# RJ45_1.net
KiCad netlist of a schematic drawn in Altium Designer
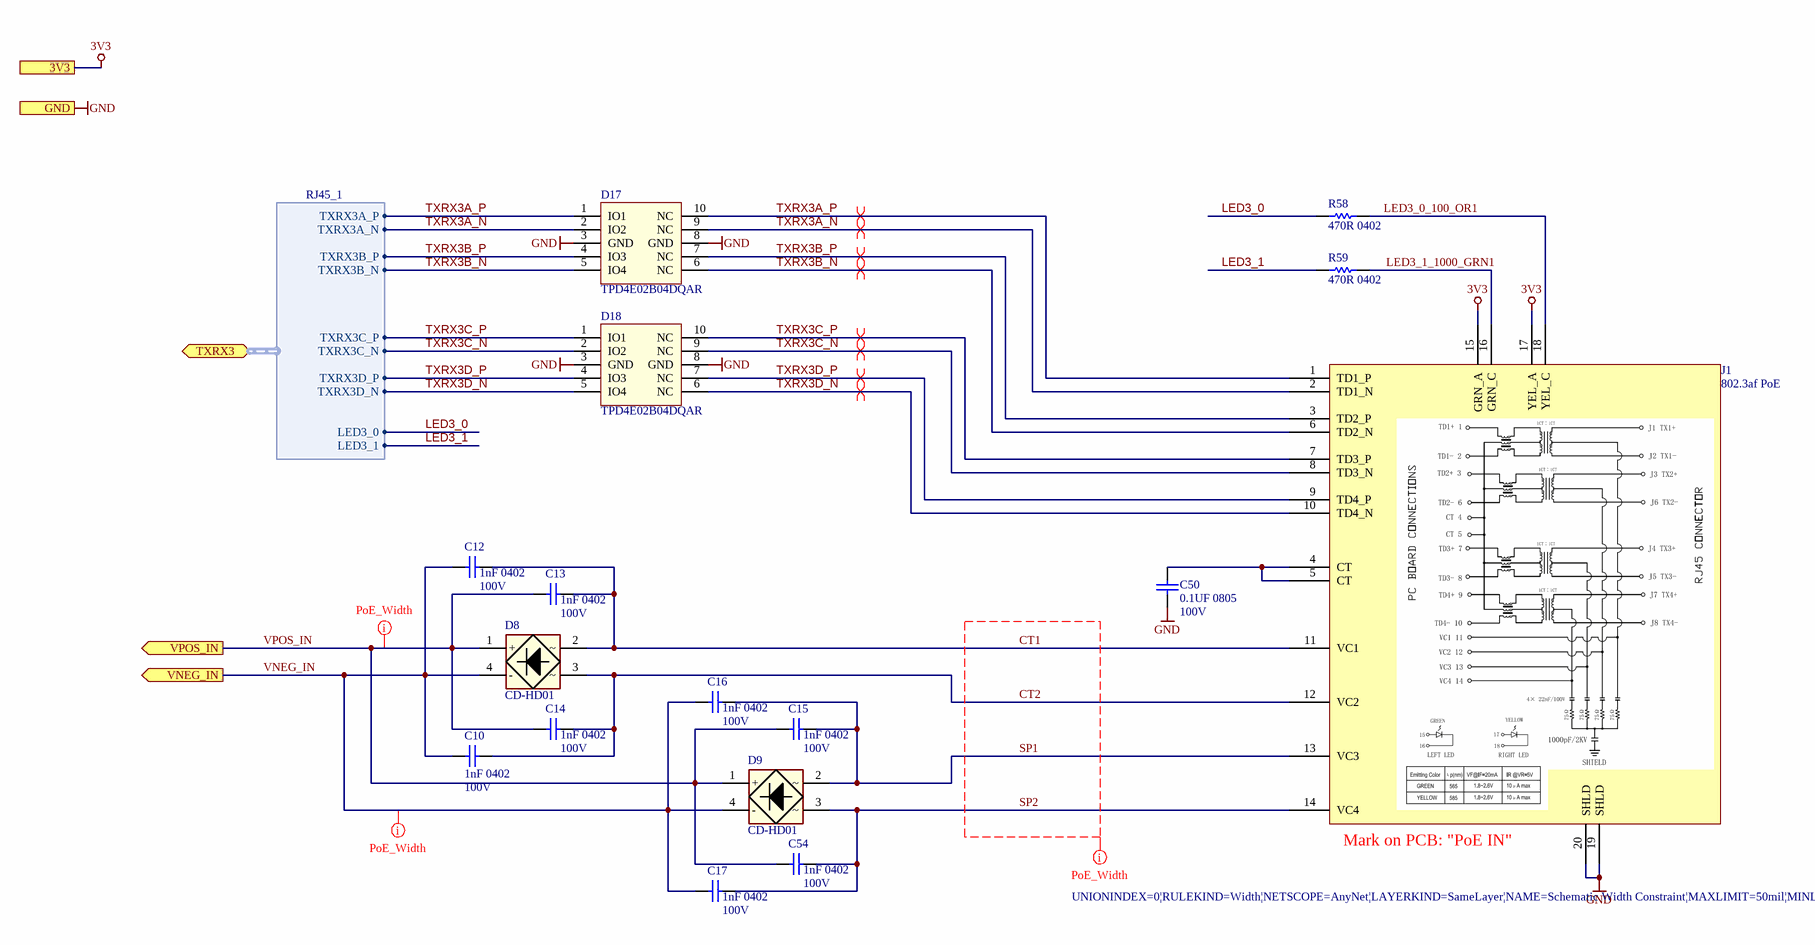
[diagram p0: RJ45_1.SchDoc]

(export (version "E")
  (design (tool "Eeschema 10.0.6"))
  (components
    (comp (ref "C10")
      (value "1nF 0402")
      (footprint "CAP_Altium_Vault_Generic:CAPC0402(1005)60_N")
      (description "CAP CER 1000PF 100V X7R 0402")
      (fields (field (name "TOLERANCE") "10%") (field (name "VOLTAGE") "100V"))
      (libsource (lib "PCBProject") (part "GRM155R72A102KA01D"))
    )
    (comp (ref "C12")
      (value "1nF 0402")
      (footprint "CAP_Altium_Vault_Generic:CAPC0402(1005)60_N")
      (description "CAP CER 1000PF 100V X7R 0402")
      (fields (field (name "TOLERANCE") "10%") (field (name "VOLTAGE") "100V"))
      (libsource (lib "PCBProject") (part "GRM155R72A102KA01D"))
    )
    (comp (ref "C13")
      (value "1nF 0402")
      (footprint "CAP_Altium_Vault_Generic:CAPC0402(1005)60_N")
      (description "CAP CER 1000PF 100V X7R 0402")
      (fields (field (name "TOLERANCE") "10%") (field (name "VOLTAGE") "100V"))
      (libsource (lib "PCBProject") (part "GRM155R72A102KA01D"))
    )
    (comp (ref "C14")
      (value "1nF 0402")
      (footprint "CAP_Altium_Vault_Generic:CAPC0402(1005)60_N")
      (description "CAP CER 1000PF 100V X7R 0402")
      (fields (field (name "TOLERANCE") "10%") (field (name "VOLTAGE") "100V"))
      (libsource (lib "PCBProject") (part "GRM155R72A102KA01D"))
    )
    (comp (ref "C15")
      (value "1nF 0402")
      (footprint "CAP_Altium_Vault_Generic:CAPC0402(1005)60_N")
      (description "CAP CER 1000PF 100V X7R 0402")
      (fields (field (name "TOLERANCE") "10%") (field (name "VOLTAGE") "100V"))
      (libsource (lib "PCBProject") (part "GRM155R72A102KA01D"))
    )
    (comp (ref "C16")
      (value "1nF 0402")
      (footprint "CAP_Altium_Vault_Generic:CAPC0402(1005)60_N")
      (description "CAP CER 1000PF 100V X7R 0402")
      (fields (field (name "TOLERANCE") "10%") (field (name "VOLTAGE") "100V"))
      (libsource (lib "PCBProject") (part "GRM155R72A102KA01D"))
    )
    (comp (ref "C17")
      (value "1nF 0402")
      (footprint "CAP_Altium_Vault_Generic:CAPC0402(1005)60_N")
      (description "CAP CER 1000PF 100V X7R 0402")
      (fields (field (name "TOLERANCE") "10%") (field (name "VOLTAGE") "100V"))
      (libsource (lib "PCBProject") (part "GRM155R72A102KA01D"))
    )
    (comp (ref "C50")
      (value "0.1UF 0805")
      (footprint "CAP_Altium_Vault_Generic:CAPC0805(2012)145_N")
      (description "CAP CER 0.1UF 100V X7R 0805")
      (fields (field (name "TOLERANCE") "10%") (field (name "VOLTAGE RATING") "100V"))
      (libsource (lib "PCBProject") (part "CL21B104KCFNNNE"))
    )
    (comp (ref "C54")
      (value "1nF 0402")
      (footprint "CAP_Altium_Vault_Generic:CAPC0402(1005)60_N")
      (description "CAP CER 1000PF 100V X7R 0402")
      (fields (field (name "TOLERANCE") "10%") (field (name "VOLTAGE") "100V"))
      (libsource (lib "PCBProject") (part "GRM155R72A102KA01D"))
    )
    (comp (ref "D8")
      (value "CD-HD01")
      (footprint "SMD-4")
      (description "CD-HD0x Series Schottky Bridge Rectifier Diode 100V 4-Pin Surface Mount T/R")
      (libsource (lib "BW2098POE_Anfa") (part "CD-HD01"))
    )
    (comp (ref "D9")
      (value "CD-HD01")
      (footprint "SMD-4")
      (description "CD-HD0x Series Schottky Bridge Rectifier Diode 100V 4-Pin Surface Mount T/R")
      (libsource (lib "BW2098POE_Anfa") (part "CD-HD01"))
    )
    (comp (ref "D17")
      (value "TPD4E02B04DQAR")
      (footprint "LuxonisMaster:TPD4E02B04DQAR")
      (libsource (lib "LuxonisMaster") (part "TPD4E02B04DQAR"))
    )
    (comp (ref "D18")
      (value "TPD4E02B04DQAR")
      (footprint "LuxonisMaster:TPD4E02B04DQAR")
      (libsource (lib "LuxonisMaster") (part "TPD4E02B04DQAR"))
    )
    (comp (ref "J1")
      (value "802.3af PoE")
      (footprint "BW2098POE:TRJG0926HENL")
      (description "CONN MAGJACK 1PORT 1000 BASET")
      (libsource (lib "BW2098POE") (part "TRJG0926HENL"))
    )
    (comp (ref "R58")
      (value "470R 0402")
      (footprint "RESC0402(1005)_N")
      (description "RES SMD 470 OHM 1% 1/16W 0402")
      (fields (field (name "TOLERANCE") "1%"))
      (libsource (lib "LuxonisMaster") (part "CRCW0402470RFKED"))
    )
    (comp (ref "R59")
      (value "470R 0402")
      (footprint "RESC0402(1005)_N")
      (description "RES SMD 470 OHM 1% 1/16W 0402")
      (fields (field (name "TOLERANCE") "1%"))
      (libsource (lib "LuxonisMaster") (part "CRCW0402470RFKED"))
    )
  )
  (nets
    (net (code "2") (name "/CT1") (class "Default")
      (node (ref "C12") (pin "1") (pinfunction "1_1") (pintype "passive"))
      (node (ref "C13") (pin "1") (pinfunction "1_1") (pintype "passive"))
      (node (ref "D8") (pin "2") (pinfunction "~_2") (pintype "passive"))
      (node (ref "J1") (pin "11") (pinfunction "VC1_11") (pintype "passive"))
    )
    (net (code "3") (name "/CT2") (class "Default")
      (node (ref "C10") (pin "1") (pinfunction "1_1") (pintype "passive"))
      (node (ref "C14") (pin "1") (pinfunction "1_1") (pintype "passive"))
      (node (ref "D8") (pin "3") (pinfunction "~_3") (pintype "passive"))
      (node (ref "J1") (pin "12") (pinfunction "VC2_12") (pintype "passive"))
    )
    (net (code "4") (name "/LED3_0") (class "Default")
      (node (ref "R58") (pin "1") (pinfunction "1_1") (pintype "passive"))
    )
    (net (code "5") (name "/LED3_0_100_OR1") (class "Default")
      (node (ref "J1") (pin "18") (pinfunction "YEL_C_18") (pintype "passive"))
      (node (ref "R58") (pin "2") (pinfunction "2_2") (pintype "passive"))
    )
    (net (code "6") (name "/LED3_1") (class "Default")
      (node (ref "R59") (pin "1") (pinfunction "1_1") (pintype "passive"))
    )
    (net (code "7") (name "/LED3_1_1000_GRN1") (class "Default")
      (node (ref "J1") (pin "16") (pinfunction "GRN_C_16") (pintype "passive"))
      (node (ref "R59") (pin "2") (pinfunction "2_2") (pintype "passive"))
    )
    (net (code "8") (name "/SP1") (class "Default")
      (node (ref "C15") (pin "1") (pinfunction "1_1") (pintype "passive"))
      (node (ref "C16") (pin "1") (pinfunction "1_1") (pintype "passive"))
      (node (ref "D9") (pin "2") (pinfunction "~_2") (pintype "passive"))
      (node (ref "J1") (pin "13") (pinfunction "VC3_13") (pintype "passive"))
    )
    (net (code "9") (name "/SP2") (class "Default")
      (node (ref "C17") (pin "1") (pinfunction "1_1") (pintype "passive"))
      (node (ref "C54") (pin "1") (pinfunction "1_1") (pintype "passive"))
      (node (ref "D9") (pin "3") (pinfunction "~_3") (pintype "passive"))
      (node (ref "J1") (pin "14") (pinfunction "VC4_14") (pintype "passive"))
    )
    (net (code "10") (name "/TXRX3A_N") (class "Default")
      (node (ref "D17") (pin "2") (pinfunction "IO2_2") (pintype "passive"))
      (node (ref "D17") (pin "9") (pinfunction "NC_9") (pintype "passive"))
      (node (ref "J1") (pin "2") (pinfunction "TD1_N_2") (pintype "passive"))
    )
    (net (code "11") (name "/TXRX3A_P") (class "Default")
      (node (ref "D17") (pin "1") (pinfunction "IO1_1") (pintype "passive"))
      (node (ref "D17") (pin "10") (pinfunction "NC_10") (pintype "passive"))
      (node (ref "J1") (pin "1") (pinfunction "TD1_P_1") (pintype "passive"))
    )
    (net (code "12") (name "/TXRX3B_N") (class "Default")
      (node (ref "D17") (pin "5") (pinfunction "IO4_5") (pintype "passive"))
      (node (ref "D17") (pin "6") (pinfunction "NC_6") (pintype "passive"))
      (node (ref "J1") (pin "6") (pinfunction "TD2_N_6") (pintype "passive"))
    )
    (net (code "13") (name "/TXRX3B_P") (class "Default")
      (node (ref "D17") (pin "4") (pinfunction "IO3_4") (pintype "passive"))
      (node (ref "D17") (pin "7") (pinfunction "NC_7") (pintype "passive"))
      (node (ref "J1") (pin "3") (pinfunction "TD2_P_3") (pintype "passive"))
    )
    (net (code "14") (name "/TXRX3C_N") (class "Default")
      (node (ref "D18") (pin "2") (pinfunction "IO2_2") (pintype "passive"))
      (node (ref "D18") (pin "9") (pinfunction "NC_9") (pintype "passive"))
      (node (ref "J1") (pin "8") (pinfunction "TD3_N_8") (pintype "passive"))
    )
    (net (code "15") (name "/TXRX3C_P") (class "Default")
      (node (ref "D18") (pin "1") (pinfunction "IO1_1") (pintype "passive"))
      (node (ref "D18") (pin "10") (pinfunction "NC_10") (pintype "passive"))
      (node (ref "J1") (pin "7") (pinfunction "TD3_P_7") (pintype "passive"))
    )
    (net (code "16") (name "/TXRX3D_N") (class "Default")
      (node (ref "D18") (pin "5") (pinfunction "IO4_5") (pintype "passive"))
      (node (ref "D18") (pin "6") (pinfunction "NC_6") (pintype "passive"))
      (node (ref "J1") (pin "10") (pinfunction "TD4_N_10") (pintype "passive"))
    )
    (net (code "17") (name "/TXRX3D_P") (class "Default")
      (node (ref "D18") (pin "4") (pinfunction "IO3_4") (pintype "passive"))
      (node (ref "D18") (pin "7") (pinfunction "NC_7") (pintype "passive"))
      (node (ref "J1") (pin "9") (pinfunction "TD4_P_9") (pintype "passive"))
    )
    (net (code "18") (name "/VNEG_IN") (class "Default")
      (node (ref "C10") (pin "2") (pinfunction "2_2") (pintype "passive"))
      (node (ref "C12") (pin "2") (pinfunction "2_2") (pintype "passive"))
      (node (ref "C16") (pin "2") (pinfunction "2_2") (pintype "passive"))
      (node (ref "C17") (pin "2") (pinfunction "2_2") (pintype "passive"))
      (node (ref "D8") (pin "4") (pinfunction "-_4") (pintype "passive"))
      (node (ref "D9") (pin "4") (pinfunction "-_4") (pintype "passive"))
    )
    (net (code "19") (name "/VPOS_IN") (class "Default")
      (node (ref "C13") (pin "2") (pinfunction "2_2") (pintype "passive"))
      (node (ref "C14") (pin "2") (pinfunction "2_2") (pintype "passive"))
      (node (ref "C15") (pin "2") (pinfunction "2_2") (pintype "passive"))
      (node (ref "C54") (pin "2") (pinfunction "2_2") (pintype "passive"))
      (node (ref "D8") (pin "1") (pinfunction "+_1") (pintype "passive"))
      (node (ref "D9") (pin "1") (pinfunction "+_1") (pintype "passive"))
    )
    (net (code "21") (name "3V3") (class "Default")
      (node (ref "J1") (pin "15") (pinfunction "GRN_A_15") (pintype "passive"))
      (node (ref "J1") (pin "17") (pinfunction "YEL_A_17") (pintype "passive"))
    )
    (net (code "22") (name "GND") (class "Default")
      (node (ref "C50") (pin "1") (pinfunction "1_1") (pintype "passive"))
      (node (ref "D17") (pin "3") (pinfunction "GND_3") (pintype "passive"))
      (node (ref "D17") (pin "8") (pinfunction "GND_8") (pintype "passive"))
      (node (ref "D18") (pin "3") (pinfunction "GND_3") (pintype "passive"))
      (node (ref "D18") (pin "8") (pinfunction "GND_8") (pintype "passive"))
      (node (ref "J1") (pin "19") (pinfunction "SHLD_19") (pintype "passive"))
      (node (ref "J1") (pin "20") (pinfunction "SHLD_20") (pintype "passive"))
    )
    (net (code "23") (name "Net-(C50-Pad2)") (class "Default")
      (node (ref "C50") (pin "2") (pinfunction "2_2") (pintype "passive"))
      (node (ref "J1") (pin "4") (pinfunction "CT_4") (pintype "passive"))
      (node (ref "J1") (pin "5") (pinfunction "CT_5") (pintype "passive"))
    )
  )
)
